# SCH_ESP32-Simplified_2024-08-01.net
KiCad netlist of a schematic drawn in EasyEDA
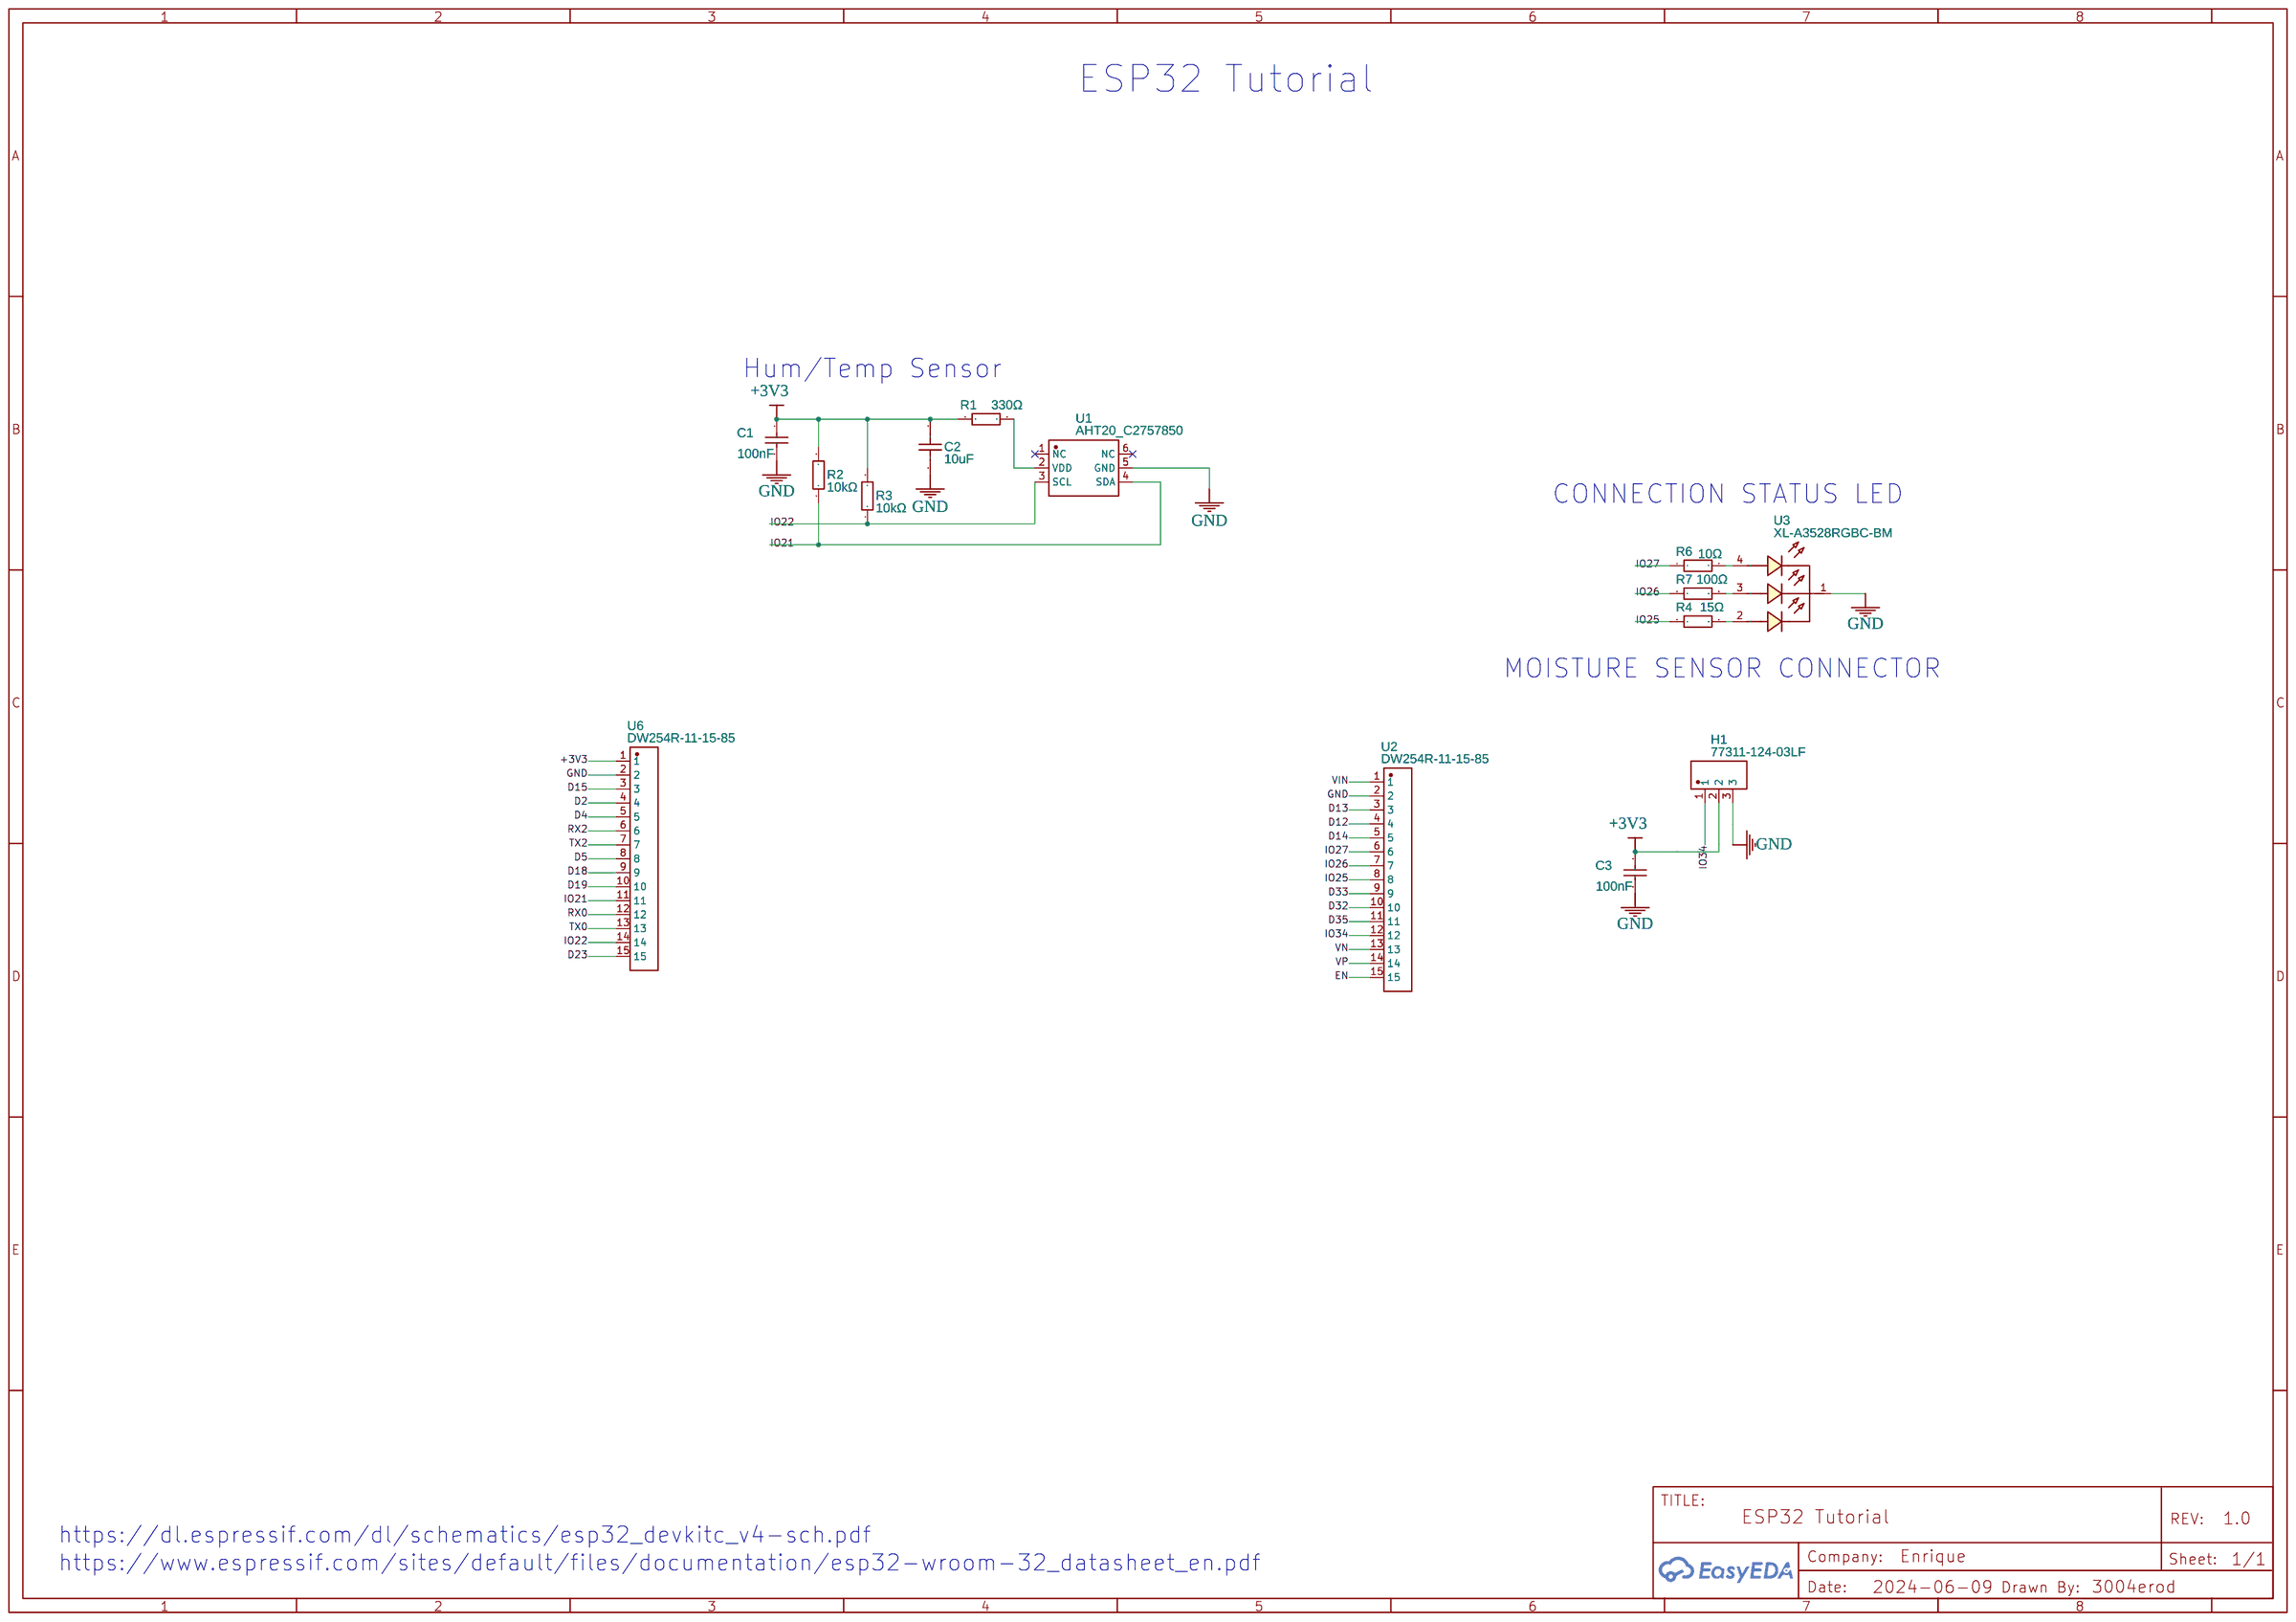
[diagram p0: schematic sheet]

(export (version "E")
  (design (tool "Eeschema 10.0.6"))
  (components
    (comp (ref "C1")
      (value "100nF")
      (fields
        (field (name "Manufacturer Part") "CL05B104KO5NNNC")
        (field (name "Manufacturer") "SAMSUNG(三星)")
      )
      (libsource (lib "") (part "CL05B104KO5NNNC"))
    )
    (comp (ref "C2")
      (value "10uF")
      (fields
        (field (name "Manufacturer Part") "CL05A106MP5NUNC")
        (field (name "Manufacturer") "SAMSUNG(三星)")
      )
      (libsource (lib "") (part "CL05A106MP5NUNC_C315248"))
    )
    (comp (ref "C3")
      (value "100nF")
      (fields
        (field (name "Manufacturer Part") "CL05B104KO5NNNC")
        (field (name "Manufacturer") "SAMSUNG(三星)")
      )
      (libsource (lib "") (part "CL05B104KO5NNNC"))
    )
    (comp (ref "H1")
      (value "77311-124-03LF")
      (fields (field (name "Manufacturer") "Amphenol"))
      (libsource (lib "") (part "77311-124-03LF"))
    )
    (comp (ref "R1")
      (value "330Ω")
      (fields
        (field (name "Manufacturer Part") "0603WAF3300T5E")
        (field (name "Manufacturer") "UNI-ROYAL(厚声)")
      )
      (libsource (lib "") (part "0603WAF3300T5E"))
    )
    (comp (ref "R2")
      (value "10kΩ")
      (fields (field (name "Manufacturer Part") "RC0402FR-0710KL") (field (name "Manufacturer") "YAGEO(国巨)"))
      (libsource (lib "") (part "RC0402FR-0710KL"))
    )
    (comp (ref "R3")
      (value "10kΩ")
      (fields (field (name "Manufacturer Part") "RC0402FR-0710KL") (field (name "Manufacturer") "YAGEO(国巨)"))
      (libsource (lib "") (part "RC0402FR-0710KL"))
    )
    (comp (ref "R4")
      (value "15Ω")
      (fields
        (field (name "Manufacturer Part") "0805W8F150JT5E")
        (field (name "Manufacturer") "UNI-ROYAL(厚声)")
      )
      (libsource (lib "") (part "0805W8F150JT5E"))
    )
    (comp (ref "R6")
      (value "10Ω")
      (fields
        (field (name "Manufacturer Part") "0603WAF100JT5E")
        (field (name "Manufacturer") "UNI-ROYAL(厚声)")
      )
      (libsource (lib "") (part "0603WAF100JT5E"))
    )
    (comp (ref "R7")
      (value "100Ω")
      (fields
        (field (name "Manufacturer Part") "0603WAF1000T5E")
        (field (name "Manufacturer") "UNI-ROYAL(厚声)")
      )
      (libsource (lib "") (part "0603WAF1000T5E"))
    )
    (comp (ref "U1")
      (value "AHT20_C2757850")
      (fields (field (name "Manufacturer Part") "AHT20") (field (name "Manufacturer") "广州奥松"))
      (libsource (lib "") (part "AHT20_C2757850"))
    )
    (comp (ref "U2")
      (value "DW254R-11-15-85")
      (fields (field (name "Manufacturer") "DEALON(德艺隆)"))
      (libsource (lib "") (part "DW254R-11-15-85"))
    )
    (comp (ref "U3")
      (value "XL-A3528RGBC-BM")
      (fields (field (name "Manufacturer") "XINGLIGHT(成兴光)"))
      (libsource (lib "") (part "XL-A3528RGBC-BM"))
    )
    (comp (ref "U6")
      (value "DW254R-11-15-85")
      (fields (field (name "Manufacturer") "DEALON(德艺隆)"))
      (libsource (lib "") (part "DW254R-11-15-85"))
    )
  )
  (nets
    (net (code "1") (name "+3V3") (class "Default")
      (node (ref "C1") (pin "1") (pinfunction "1_1") (pintype "input"))
      (node (ref "C2") (pin "2") (pinfunction "2_2") (pintype "unspecified"))
      (node (ref "C3") (pin "1") (pinfunction "1_1") (pintype "input"))
      (node (ref "H1") (pin "2") (pinfunction "2_2") (pintype "unspecified"))
      (node (ref "R1") (pin "1") (pinfunction "1_1") (pintype "input"))
      (node (ref "R2") (pin "2") (pinfunction "2_2") (pintype "input"))
      (node (ref "R3") (pin "2") (pinfunction "2_2") (pintype "input"))
      (node (ref "U6") (pin "1") (pinfunction "1_1") (pintype "unspecified"))
    )
    (net (code "2") (name "/D2") (class "Default")
      (node (ref "U6") (pin "4") (pinfunction "4_4") (pintype "unspecified"))
    )
    (net (code "3") (name "/D4") (class "Default")
      (node (ref "U6") (pin "5") (pinfunction "5_5") (pintype "unspecified"))
    )
    (net (code "4") (name "/D5") (class "Default")
      (node (ref "U6") (pin "8") (pinfunction "8_8") (pintype "unspecified"))
    )
    (net (code "5") (name "/D12") (class "Default")
      (node (ref "U2") (pin "4") (pinfunction "4_4") (pintype "unspecified"))
    )
    (net (code "6") (name "/D13") (class "Default")
      (node (ref "U2") (pin "3") (pinfunction "3_3") (pintype "unspecified"))
    )
    (net (code "7") (name "/D14") (class "Default")
      (node (ref "U2") (pin "5") (pinfunction "5_5") (pintype "unspecified"))
    )
    (net (code "8") (name "/D15") (class "Default")
      (node (ref "U6") (pin "3") (pinfunction "3_3") (pintype "unspecified"))
    )
    (net (code "9") (name "/D18") (class "Default")
      (node (ref "U6") (pin "9") (pinfunction "9_9") (pintype "unspecified"))
    )
    (net (code "10") (name "/D19") (class "Default")
      (node (ref "U6") (pin "10") (pinfunction "10_10") (pintype "unspecified"))
    )
    (net (code "11") (name "/D23") (class "Default")
      (node (ref "U6") (pin "15") (pinfunction "15_15") (pintype "unspecified"))
    )
    (net (code "12") (name "/D32") (class "Default")
      (node (ref "U2") (pin "10") (pinfunction "10_10") (pintype "unspecified"))
    )
    (net (code "13") (name "/D33") (class "Default")
      (node (ref "U2") (pin "9") (pinfunction "9_9") (pintype "unspecified"))
    )
    (net (code "14") (name "/D35") (class "Default")
      (node (ref "U2") (pin "11") (pinfunction "11_11") (pintype "unspecified"))
    )
    (net (code "15") (name "/EN") (class "Default")
      (node (ref "U2") (pin "15") (pinfunction "15_15") (pintype "unspecified"))
    )
    (net (code "16") (name "/IO21") (class "Default")
      (node (ref "R2") (pin "1") (pinfunction "1_1") (pintype "input"))
      (node (ref "U1") (pin "4") (pinfunction "SDA_4") (pintype "unspecified"))
      (node (ref "U6") (pin "11") (pinfunction "11_11") (pintype "unspecified"))
    )
    (net (code "17") (name "/IO22") (class "Default")
      (node (ref "R3") (pin "1") (pinfunction "1_1") (pintype "input"))
      (node (ref "U1") (pin "3") (pinfunction "SCL_3") (pintype "unspecified"))
      (node (ref "U6") (pin "14") (pinfunction "14_14") (pintype "unspecified"))
    )
    (net (code "18") (name "/IO25") (class "Default")
      (node (ref "R4") (pin "1") (pinfunction "1_1") (pintype "input"))
      (node (ref "U2") (pin "8") (pinfunction "8_8") (pintype "unspecified"))
    )
    (net (code "19") (name "/IO26") (class "Default")
      (node (ref "R7") (pin "1") (pinfunction "1_1") (pintype "input"))
      (node (ref "U2") (pin "7") (pinfunction "7_7") (pintype "unspecified"))
    )
    (net (code "20") (name "/IO27") (class "Default")
      (node (ref "R6") (pin "1") (pinfunction "1_1") (pintype "input"))
      (node (ref "U2") (pin "6") (pinfunction "6_6") (pintype "unspecified"))
    )
    (net (code "21") (name "/IO34") (class "Default")
      (node (ref "H1") (pin "1") (pinfunction "1_1") (pintype "unspecified"))
      (node (ref "U2") (pin "12") (pinfunction "12_12") (pintype "unspecified"))
    )
    (net (code "22") (name "/RX0") (class "Default")
      (node (ref "U6") (pin "12") (pinfunction "12_12") (pintype "unspecified"))
    )
    (net (code "23") (name "/RX2") (class "Default")
      (node (ref "U6") (pin "6") (pinfunction "6_6") (pintype "unspecified"))
    )
    (net (code "24") (name "/TX0") (class "Default")
      (node (ref "U6") (pin "13") (pinfunction "13_13") (pintype "unspecified"))
    )
    (net (code "25") (name "/TX2") (class "Default")
      (node (ref "U6") (pin "7") (pinfunction "7_7") (pintype "unspecified"))
    )
    (net (code "26") (name "/VIN") (class "Default")
      (node (ref "U2") (pin "1") (pinfunction "1_1") (pintype "unspecified"))
    )
    (net (code "27") (name "/VN") (class "Default")
      (node (ref "U2") (pin "13") (pinfunction "13_13") (pintype "unspecified"))
    )
    (net (code "28") (name "/VP") (class "Default")
      (node (ref "U2") (pin "14") (pinfunction "14_14") (pintype "unspecified"))
    )
    (net (code "29") (name "GND") (class "Default")
      (node (ref "C1") (pin "2") (pinfunction "2_2") (pintype "input"))
      (node (ref "C2") (pin "1") (pinfunction "1_1") (pintype "unspecified"))
      (node (ref "C3") (pin "2") (pinfunction "2_2") (pintype "input"))
      (node (ref "H1") (pin "3") (pinfunction "3_3") (pintype "unspecified"))
      (node (ref "U1") (pin "5") (pinfunction "GND_5") (pintype "unspecified"))
      (node (ref "U2") (pin "2") (pinfunction "2_2") (pintype "unspecified"))
      (node (ref "U3") (pin "1") (pinfunction "1_1") (pintype "unspecified"))
      (node (ref "U6") (pin "2") (pinfunction "2_2") (pintype "unspecified"))
    )
    (net (code "30") (name "Net-(R4-Pad2)") (class "Default")
      (node (ref "R4") (pin "2") (pinfunction "2_2") (pintype "input"))
      (node (ref "U3") (pin "2") (pinfunction "2_2") (pintype "unspecified"))
    )
    (net (code "31") (name "Net-(R6-Pad2)") (class "Default")
      (node (ref "R6") (pin "2") (pinfunction "2_2") (pintype "input"))
      (node (ref "U3") (pin "4") (pinfunction "4_4") (pintype "unspecified"))
    )
    (net (code "32") (name "Net-(R7-Pad2)") (class "Default")
      (node (ref "R7") (pin "2") (pinfunction "2_2") (pintype "input"))
      (node (ref "U3") (pin "3") (pinfunction "3_3") (pintype "unspecified"))
    )
    (net (code "33") (name "Net-(U1-VDD)") (class "Default")
      (node (ref "R1") (pin "2") (pinfunction "2_2") (pintype "input"))
      (node (ref "U1") (pin "2") (pinfunction "VDD_2") (pintype "unspecified"))
    )
    (net (code "34") (name "unconnected-(U1-NC-Pad1)") (class "Default")
      (node (ref "U1") (pin "1") (pinfunction "NC_1") (pintype "unspecified+no_connect"))
    )
    (net (code "35") (name "unconnected-(U1-NC-Pad6)") (class "Default")
      (node (ref "U1") (pin "6") (pinfunction "NC_6") (pintype "unspecified+no_connect"))
    )
  )
)
